# Sheet1.net
KiCad netlist of a schematic drawn in Altium Designer
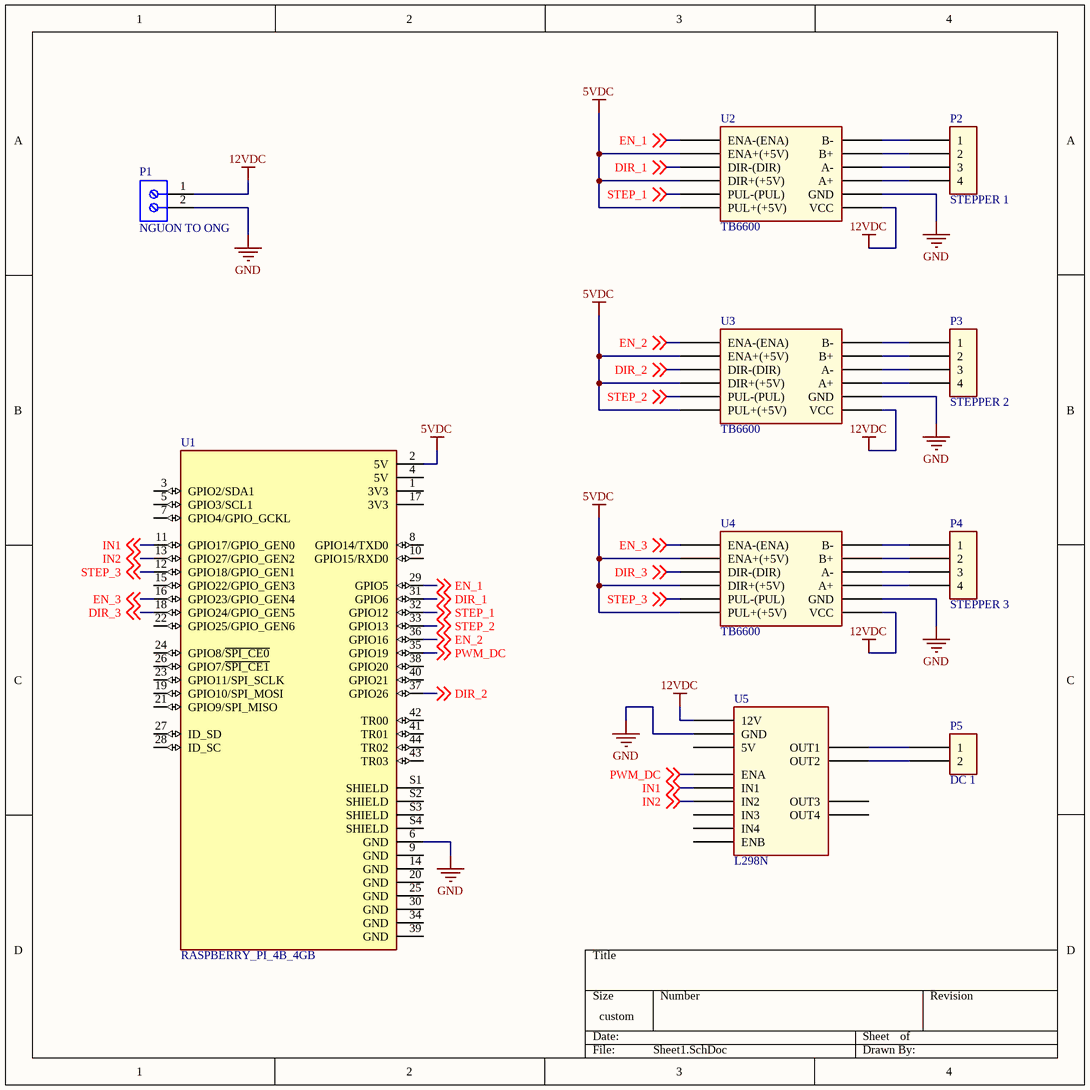
[diagram p0: Sheet1.SchDoc]

(export (version "E")
  (design (tool "Eeschema 10.0.6"))
  (components
    (comp (ref "P1")
      (value "NGUON TO ONG")
      (footprint "DOMINO_2")
      (description "Domino 2")
      (libsource (lib "SachTran_Lib") (part "DOMINO_2"))
    )
    (comp (ref "P2")
      (value "STEPPER 1")
      (footprint "CON4")
      (description "Connector 4")
      (libsource (lib "SachTran_Lib") (part "CON4"))
    )
    (comp (ref "P3")
      (value "STEPPER 2")
      (footprint "CON4")
      (description "Connector 4")
      (libsource (lib "SachTran_Lib") (part "CON4"))
    )
    (comp (ref "P4")
      (value "STEPPER 3")
      (footprint "CON4")
      (description "Connector 4")
      (libsource (lib "SachTran_Lib") (part "CON4"))
    )
    (comp (ref "P5")
      (value "DC 1")
      (footprint "CON2")
      (description "Connector 2")
      (libsource (lib "SachTran_Lib") (part "CON2"))
    )
    (comp (ref "U1")
      (value "RASPBERRY_PI_4B_4GB")
      (footprint "MODULE_RASPBERRY_PI_4B_4GB")
      (description "Raspberry Pi 4 Model B 4GB")
      (fields (field (name "MF") "Raspberry Pi") (field (name "MP") "RASPBERRY PI 4B/4GB"))
      (libsource (lib "SachTran_Lib") (part "RASPBERRY_PI_4B_4GB"))
    )
    (comp (ref "U2")
      (value "TB6600")
      (footprint "TB6600")
      (description "Driver Steppter TB6600")
      (libsource (lib "SachTran_Lib") (part "TB6600"))
    )
    (comp (ref "U3")
      (value "TB6600")
      (footprint "TB6600")
      (description "Driver Steppter TB6600")
      (libsource (lib "SachTran_Lib") (part "TB6600"))
    )
    (comp (ref "U4")
      (value "TB6600")
      (footprint "TB6600")
      (description "Driver Steppter TB6600")
      (libsource (lib "SachTran_Lib") (part "TB6600"))
    )
    (comp (ref "U5") (value "L298N") (footprint "L298N") (libsource (lib "SachTran_Lib") (part "L298N")))
  )
  (nets
    (net (code "1") (name "5VDC") (class "Default")
      (node (ref "U1") (pin "2") (pinfunction "5V_2") (pintype "power_in"))
      (node (ref "U2") (pin "1") (pinfunction "ENA+(+5V)_1") (pintype "passive"))
      (node (ref "U3") (pin "1") (pinfunction "ENA+(+5V)_1") (pintype "passive"))
      (node (ref "U4") (pin "1") (pinfunction "ENA+(+5V)_1") (pintype "passive"))
    )
    (net (code "2") (name "12VDC") (class "Default")
      (node (ref "P1") (pin "1") (pinfunction "1_1") (pintype "passive"))
      (node (ref "U2") (pin "1") (pinfunction "VCC_1") (pintype "passive"))
      (node (ref "U3") (pin "1") (pinfunction "VCC_1") (pintype "passive"))
      (node (ref "U4") (pin "1") (pinfunction "VCC_1") (pintype "passive"))
      (node (ref "U5") (pin "1") (pinfunction "12V_1") (pintype "passive"))
    )
    (net (code "3") (name "DIR_1") (class "Default")
      (node (ref "U1") (pin "31") (pinfunction "GPIO6_31") (pintype "bidirectional"))
      (node (ref "U2") (pin "1") (pinfunction "DIR-(DIR)_1") (pintype "passive"))
    )
    (net (code "4") (name "DIR_2") (class "Default")
      (node (ref "U1") (pin "37") (pinfunction "GPIO26_37") (pintype "bidirectional"))
      (node (ref "U3") (pin "1") (pinfunction "DIR-(DIR)_1") (pintype "passive"))
    )
    (net (code "5") (name "DIR_3") (class "Default")
      (node (ref "U1") (pin "18") (pinfunction "GPIO24/GPIO_GEN5_18") (pintype "bidirectional"))
      (node (ref "U4") (pin "1") (pinfunction "DIR-(DIR)_1") (pintype "passive"))
    )
    (net (code "6") (name "EN_1") (class "Default")
      (node (ref "U1") (pin "29") (pinfunction "GPIO5_29") (pintype "bidirectional"))
      (node (ref "U2") (pin "1") (pinfunction "ENA-(ENA)_1") (pintype "passive"))
    )
    (net (code "7") (name "EN_2") (class "Default")
      (node (ref "U1") (pin "36") (pinfunction "GPIO16_36") (pintype "bidirectional"))
      (node (ref "U3") (pin "1") (pinfunction "ENA-(ENA)_1") (pintype "passive"))
    )
    (net (code "8") (name "EN_3") (class "Default")
      (node (ref "U1") (pin "16") (pinfunction "GPIO23/GPIO_GEN4_16") (pintype "bidirectional"))
      (node (ref "U4") (pin "1") (pinfunction "ENA-(ENA)_1") (pintype "passive"))
    )
    (net (code "9") (name "GND") (class "Default")
      (node (ref "P1") (pin "2") (pinfunction "2_2") (pintype "passive"))
      (node (ref "U1") (pin "6") (pinfunction "GND_6") (pintype "power_in"))
      (node (ref "U2") (pin "1") (pinfunction "GND_1") (pintype "passive"))
      (node (ref "U3") (pin "1") (pinfunction "GND_1") (pintype "passive"))
      (node (ref "U4") (pin "1") (pinfunction "GND_1") (pintype "passive"))
      (node (ref "U5") (pin "1") (pinfunction "GND_1") (pintype "passive"))
    )
    (net (code "10") (name "IN1") (class "Default")
      (node (ref "U1") (pin "11") (pinfunction "GPIO17/GPIO_GEN0_11") (pintype "bidirectional"))
      (node (ref "U5") (pin "1") (pinfunction "IN1_1") (pintype "passive"))
    )
    (net (code "11") (name "IN2") (class "Default")
      (node (ref "U1") (pin "13") (pinfunction "GPIO27/GPIO_GEN2_13") (pintype "bidirectional"))
      (node (ref "U5") (pin "1") (pinfunction "IN2_1") (pintype "passive"))
    )
    (net (code "12") (name "Net-(U2-A+)") (class "Default")
      (node (ref "P2") (pin "4") (pinfunction "4_4") (pintype "passive"))
      (node (ref "U2") (pin "1") (pinfunction "A+_1") (pintype "passive"))
    )
    (net (code "13") (name "Net-(U2-A-)") (class "Default")
      (node (ref "P2") (pin "3") (pinfunction "3_3") (pintype "passive"))
      (node (ref "U2") (pin "1") (pinfunction "A-_1") (pintype "passive"))
    )
    (net (code "14") (name "Net-(U2-B+)") (class "Default")
      (node (ref "P2") (pin "2") (pinfunction "2_2") (pintype "passive"))
      (node (ref "U2") (pin "1") (pinfunction "B+_1") (pintype "passive"))
    )
    (net (code "15") (name "Net-(U2-B-)") (class "Default")
      (node (ref "P2") (pin "1") (pinfunction "1_1") (pintype "passive"))
      (node (ref "U2") (pin "1") (pinfunction "B-_1") (pintype "passive"))
    )
    (net (code "16") (name "Net-(U3-A+)") (class "Default")
      (node (ref "P3") (pin "4") (pinfunction "4_4") (pintype "passive"))
      (node (ref "U3") (pin "1") (pinfunction "A+_1") (pintype "passive"))
    )
    (net (code "17") (name "Net-(U3-A-)") (class "Default")
      (node (ref "P3") (pin "3") (pinfunction "3_3") (pintype "passive"))
      (node (ref "U3") (pin "1") (pinfunction "A-_1") (pintype "passive"))
    )
    (net (code "18") (name "Net-(U3-B+)") (class "Default")
      (node (ref "P3") (pin "2") (pinfunction "2_2") (pintype "passive"))
      (node (ref "U3") (pin "1") (pinfunction "B+_1") (pintype "passive"))
    )
    (net (code "19") (name "Net-(U3-B-)") (class "Default")
      (node (ref "P3") (pin "1") (pinfunction "1_1") (pintype "passive"))
      (node (ref "U3") (pin "1") (pinfunction "B-_1") (pintype "passive"))
    )
    (net (code "20") (name "Net-(U4-A+)") (class "Default")
      (node (ref "P4") (pin "4") (pinfunction "4_4") (pintype "passive"))
      (node (ref "U4") (pin "1") (pinfunction "A+_1") (pintype "passive"))
    )
    (net (code "21") (name "Net-(U4-A-)") (class "Default")
      (node (ref "P4") (pin "3") (pinfunction "3_3") (pintype "passive"))
      (node (ref "U4") (pin "1") (pinfunction "A-_1") (pintype "passive"))
    )
    (net (code "22") (name "Net-(U4-B+)") (class "Default")
      (node (ref "P4") (pin "2") (pinfunction "2_2") (pintype "passive"))
      (node (ref "U4") (pin "1") (pinfunction "B+_1") (pintype "passive"))
    )
    (net (code "23") (name "Net-(U4-B-)") (class "Default")
      (node (ref "P4") (pin "1") (pinfunction "1_1") (pintype "passive"))
      (node (ref "U4") (pin "1") (pinfunction "B-_1") (pintype "passive"))
    )
    (net (code "24") (name "Net-(U5-OUT1)") (class "Default")
      (node (ref "P5") (pin "1") (pinfunction "1_1") (pintype "passive"))
      (node (ref "U5") (pin "1") (pinfunction "OUT1_1") (pintype "passive"))
    )
    (net (code "25") (name "Net-(U5-OUT2)") (class "Default")
      (node (ref "P5") (pin "2") (pinfunction "2_2") (pintype "passive"))
      (node (ref "U5") (pin "1") (pinfunction "OUT2_1") (pintype "passive"))
    )
    (net (code "26") (name "PWM_DC") (class "Default")
      (node (ref "U1") (pin "35") (pinfunction "GPIO19_35") (pintype "bidirectional"))
      (node (ref "U5") (pin "1") (pinfunction "ENA_1") (pintype "passive"))
    )
    (net (code "27") (name "STEP_1") (class "Default")
      (node (ref "U1") (pin "32") (pinfunction "GPIO12_32") (pintype "bidirectional"))
      (node (ref "U2") (pin "1") (pinfunction "PUL-(PUL)_1") (pintype "passive"))
    )
    (net (code "28") (name "STEP_2") (class "Default")
      (node (ref "U1") (pin "33") (pinfunction "GPIO13_33") (pintype "bidirectional"))
      (node (ref "U3") (pin "1") (pinfunction "PUL-(PUL)_1") (pintype "passive"))
    )
    (net (code "29") (name "STEP_3") (class "Default")
      (node (ref "U1") (pin "12") (pinfunction "GPIO18/GPIO_GEN1_12") (pintype "bidirectional"))
      (node (ref "U4") (pin "1") (pinfunction "PUL-(PUL)_1") (pintype "passive"))
    )
    (net (code "30") (name "unconnected-(U1-3V3-Pad1)") (class "Default")
      (node (ref "U1") (pin "1") (pinfunction "3V3_1") (pintype "power_in"))
    )
    (net (code "31") (name "unconnected-(U1-3V3-Pad17)") (class "Default")
      (node (ref "U1") (pin "17") (pinfunction "3V3_17") (pintype "power_in"))
    )
    (net (code "32") (name "unconnected-(U1-5V-Pad4)") (class "Default")
      (node (ref "U1") (pin "4") (pinfunction "5V_4") (pintype "power_in"))
    )
    (net (code "33") (name "unconnected-(U1-GND-Pad9)") (class "Default")
      (node (ref "U1") (pin "9") (pinfunction "GND_9") (pintype "power_in"))
    )
    (net (code "34") (name "unconnected-(U1-GND-Pad14)") (class "Default")
      (node (ref "U1") (pin "14") (pinfunction "GND_14") (pintype "power_in"))
    )
    (net (code "35") (name "unconnected-(U1-GND-Pad20)") (class "Default")
      (node (ref "U1") (pin "20") (pinfunction "GND_20") (pintype "power_in"))
    )
    (net (code "36") (name "unconnected-(U1-GND-Pad25)") (class "Default")
      (node (ref "U1") (pin "25") (pinfunction "GND_25") (pintype "power_in"))
    )
    (net (code "37") (name "unconnected-(U1-GND-Pad30)") (class "Default")
      (node (ref "U1") (pin "30") (pinfunction "GND_30") (pintype "power_in"))
    )
    (net (code "38") (name "unconnected-(U1-GND-Pad34)") (class "Default")
      (node (ref "U1") (pin "34") (pinfunction "GND_34") (pintype "power_in"))
    )
    (net (code "39") (name "unconnected-(U1-GND-Pad39)") (class "Default")
      (node (ref "U1") (pin "39") (pinfunction "GND_39") (pintype "power_in"))
    )
    (net (code "40") (name "unconnected-(U1-GPIO2{slash}SDA1-Pad3)") (class "Default")
      (node (ref "U1") (pin "3") (pinfunction "GPIO2/SDA1_3") (pintype "bidirectional"))
    )
    (net (code "41") (name "unconnected-(U1-GPIO3{slash}SCL1-Pad5)") (class "Default")
      (node (ref "U1") (pin "5") (pinfunction "GPIO3/SCL1_5") (pintype "bidirectional"))
    )
    (net (code "42") (name "unconnected-(U1-GPIO4{slash}GPIO_GCKL-Pad7)") (class "Default")
      (node (ref "U1") (pin "7") (pinfunction "GPIO4/GPIO_GCKL_7") (pintype "bidirectional"))
    )
    (net (code "43") (name "unconnected-(U1-GPIO7{slash}~{SPI_CE1}-Pad26)") (class "Default")
      (node (ref "U1") (pin "26") (pinfunction "GPIO7/~{SPI_CE1}_26") (pintype "bidirectional"))
    )
    (net (code "44") (name "unconnected-(U1-GPIO8{slash}~{SPI_CE0}-Pad24)") (class "Default")
      (node (ref "U1") (pin "24") (pinfunction "GPIO8/~{SPI_CE0}_24") (pintype "bidirectional"))
    )
    (net (code "45") (name "unconnected-(U1-GPIO9{slash}SPI_MISO-Pad21)") (class "Default")
      (node (ref "U1") (pin "21") (pinfunction "GPIO9/SPI_MISO_21") (pintype "bidirectional"))
    )
    (net (code "46") (name "unconnected-(U1-GPIO10{slash}SPI_MOSI-Pad19)") (class "Default")
      (node (ref "U1") (pin "19") (pinfunction "GPIO10/SPI_MOSI_19") (pintype "bidirectional"))
    )
    (net (code "47") (name "unconnected-(U1-GPIO11{slash}SPI_SCLK-Pad23)") (class "Default")
      (node (ref "U1") (pin "23") (pinfunction "GPIO11/SPI_SCLK_23") (pintype "bidirectional"))
    )
    (net (code "48") (name "unconnected-(U1-GPIO14{slash}TXD0-Pad8)") (class "Default")
      (node (ref "U1") (pin "8") (pinfunction "GPIO14/TXD0_8") (pintype "bidirectional"))
    )
    (net (code "49") (name "unconnected-(U1-GPIO15{slash}RXD0-Pad10)") (class "Default")
      (node (ref "U1") (pin "10") (pinfunction "GPIO15/RXD0_10") (pintype "bidirectional"))
    )
    (net (code "50") (name "unconnected-(U1-GPIO20-Pad38)") (class "Default")
      (node (ref "U1") (pin "38") (pinfunction "GPIO20_38") (pintype "bidirectional"))
    )
    (net (code "51") (name "unconnected-(U1-GPIO21-Pad40)") (class "Default")
      (node (ref "U1") (pin "40") (pinfunction "GPIO21_40") (pintype "bidirectional"))
    )
    (net (code "52") (name "unconnected-(U1-GPIO22{slash}GPIO_GEN3-Pad15)") (class "Default")
      (node (ref "U1") (pin "15") (pinfunction "GPIO22/GPIO_GEN3_15") (pintype "bidirectional"))
    )
    (net (code "53") (name "unconnected-(U1-GPIO25{slash}GPIO_GEN6-Pad22)") (class "Default")
      (node (ref "U1") (pin "22") (pinfunction "GPIO25/GPIO_GEN6_22") (pintype "bidirectional"))
    )
    (net (code "54") (name "unconnected-(U1-ID_SC-Pad28)") (class "Default")
      (node (ref "U1") (pin "28") (pinfunction "ID_SC_28") (pintype "bidirectional"))
    )
    (net (code "55") (name "unconnected-(U1-ID_SD-Pad27)") (class "Default")
      (node (ref "U1") (pin "27") (pinfunction "ID_SD_27") (pintype "bidirectional"))
    )
    (net (code "56") (name "unconnected-(U1-SHIELD-PadS1)") (class "Default")
      (node (ref "U1") (pin "S1") (pinfunction "SHIELD_S1") (pintype "power_in"))
    )
    (net (code "57") (name "unconnected-(U1-SHIELD-PadS2)") (class "Default")
      (node (ref "U1") (pin "S2") (pinfunction "SHIELD_S2") (pintype "power_in"))
    )
    (net (code "58") (name "unconnected-(U1-SHIELD-PadS3)") (class "Default")
      (node (ref "U1") (pin "S3") (pinfunction "SHIELD_S3") (pintype "power_in"))
    )
    (net (code "59") (name "unconnected-(U1-SHIELD-PadS4)") (class "Default")
      (node (ref "U1") (pin "S4") (pinfunction "SHIELD_S4") (pintype "power_in"))
    )
    (net (code "60") (name "unconnected-(U1-TR00-Pad42)") (class "Default")
      (node (ref "U1") (pin "42") (pinfunction "TR00_42") (pintype "bidirectional"))
    )
    (net (code "61") (name "unconnected-(U1-TR01-Pad41)") (class "Default")
      (node (ref "U1") (pin "41") (pinfunction "TR01_41") (pintype "bidirectional"))
    )
    (net (code "62") (name "unconnected-(U1-TR02-Pad44)") (class "Default")
      (node (ref "U1") (pin "44") (pinfunction "TR02_44") (pintype "bidirectional"))
    )
    (net (code "63") (name "unconnected-(U1-TR03-Pad43)") (class "Default")
      (node (ref "U1") (pin "43") (pinfunction "TR03_43") (pintype "bidirectional"))
    )
    (net (code "64") (name "unconnected-(U5-5V-Pad1)") (class "Default")
      (node (ref "U5") (pin "1") (pinfunction "5V_1") (pintype "passive"))
    )
    (net (code "65") (name "unconnected-(U5-ENB-Pad1)") (class "Default")
      (node (ref "U5") (pin "1") (pinfunction "ENB_1") (pintype "passive"))
    )
    (net (code "66") (name "unconnected-(U5-IN3-Pad1)") (class "Default")
      (node (ref "U5") (pin "1") (pinfunction "IN3_1") (pintype "passive"))
    )
    (net (code "67") (name "unconnected-(U5-IN4-Pad1)") (class "Default")
      (node (ref "U5") (pin "1") (pinfunction "IN4_1") (pintype "passive"))
    )
    (net (code "68") (name "unconnected-(U5-OUT3-Pad1)") (class "Default")
      (node (ref "U5") (pin "1") (pinfunction "OUT3_1") (pintype "passive"))
    )
    (net (code "69") (name "unconnected-(U5-OUT4-Pad1)") (class "Default")
      (node (ref "U5") (pin "1") (pinfunction "OUT4_1") (pintype "passive"))
    )
  )
)
